# rev2.net
KiCad netlist of a schematic drawn in EAGLE
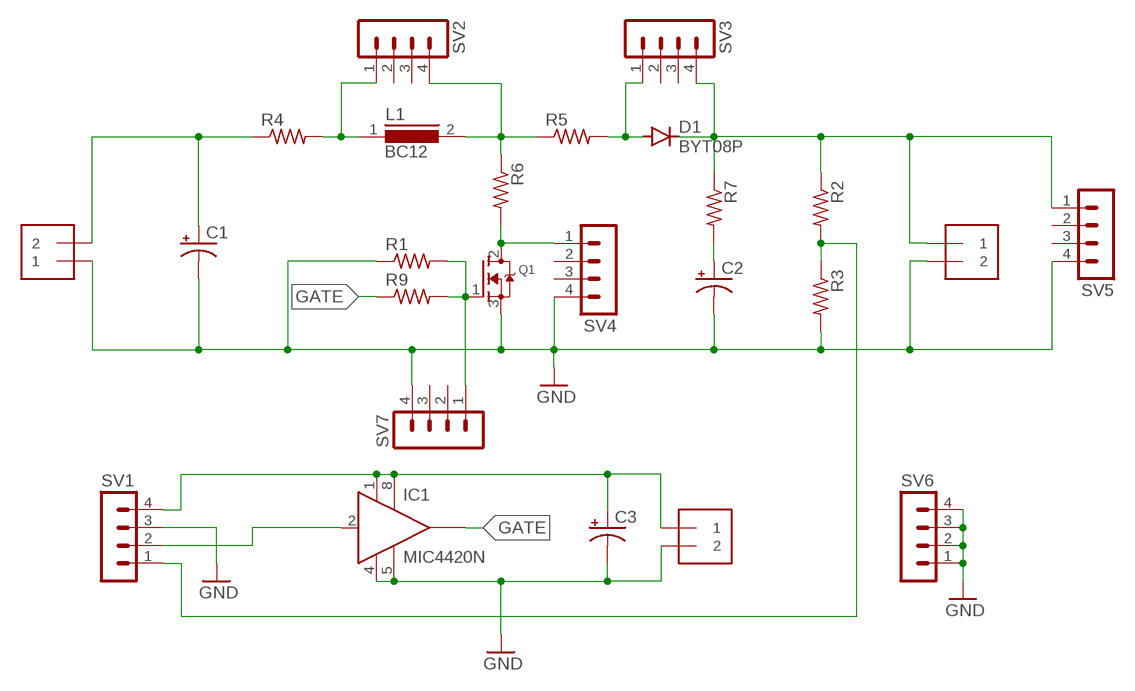
[diagram p0: schematic, sheet 1]

(export (version "E")
  (design (tool "Eeschema 10.0.6"))
  (components
    (comp (ref "C1")
      (value "CPOL-USE7.5-18")
      (footprint "eagle-import:E7,5-18")
      (libsource (lib "eagle-import") (part "CPOL-USE7.5-18"))
    )
    (comp (ref "C2")
      (value "CPOL-USE7.5-18")
      (footprint "eagle-import:E7,5-18")
      (libsource (lib "eagle-import") (part "CPOL-USE7.5-18"))
    )
    (comp (ref "C3")
      (value "CPOL-USE2.5-6")
      (footprint "eagle-import:E2,5-6")
      (libsource (lib "eagle-import") (part "CPOL-USE2.5-6"))
    )
    (comp (ref "D1")
      (value "BYT08P")
      (footprint "eagle-import:TO220ACS")
      (libsource (lib "eagle-import") (part "BYT08P"))
    )
    (comp (ref "IC1")
      (value "MIC4420N")
      (footprint "eagle-import:DIL08")
      (libsource (lib "eagle-import") (part "MIC4420N"))
    )
    (comp (ref "J1")
      (value "1X2-3.5MM")
      (footprint "eagle-import:1X2-3.5MM")
      (libsource (lib "eagle-import") (part "1X2-3.5MM"))
    )
    (comp (ref "J2")
      (value "1X2-3.5MM")
      (footprint "eagle-import:1X2-3.5MM")
      (libsource (lib "eagle-import") (part "1X2-3.5MM"))
    )
    (comp (ref "J3")
      (value "1X2-3.5MM")
      (footprint "eagle-import:1X2-3.5MM")
      (libsource (lib "eagle-import") (part "1X2-3.5MM"))
    )
    (comp (ref "L1")
      (value "BC12")
      (footprint "eagle-import:BC12")
      (libsource (lib "eagle-import") (part "BC12"))
    )
    (comp (ref "Q1")
      (value "MOSFET-NGDS_TO220V")
      (footprint "eagle-import:TO220V")
      (libsource (lib "eagle-import") (part "MOSFET-NGDS_TO220V"))
    )
    (comp (ref "R1")
      (value "R-US_0207/7")
      (footprint "eagle-import:0207_7")
      (libsource (lib "eagle-import") (part "R-US_0207/7"))
    )
    (comp (ref "R2")
      (value "R-US_0207/7")
      (footprint "eagle-import:0207_7")
      (libsource (lib "eagle-import") (part "R-US_0207/7"))
    )
    (comp (ref "R3")
      (value "R-US_0207/7")
      (footprint "eagle-import:0207_7")
      (libsource (lib "eagle-import") (part "R-US_0207/7"))
    )
    (comp (ref "R4")
      (value "R-US_0613/15")
      (footprint "eagle-import:P0613_15")
      (libsource (lib "eagle-import") (part "R-US_0613/15"))
    )
    (comp (ref "R5")
      (value "R-US_0613/15")
      (footprint "eagle-import:P0613_15")
      (libsource (lib "eagle-import") (part "R-US_0613/15"))
    )
    (comp (ref "R6")
      (value "R-US_0613/15")
      (footprint "eagle-import:P0613_15")
      (libsource (lib "eagle-import") (part "R-US_0613/15"))
    )
    (comp (ref "R7")
      (value "R-US_0613/15")
      (footprint "eagle-import:P0613_15")
      (libsource (lib "eagle-import") (part "R-US_0613/15"))
    )
    (comp (ref "R9")
      (value "R-US_0309/12")
      (footprint "eagle-import:0309_12")
      (libsource (lib "eagle-import") (part "R-US_0309/12"))
    )
    (comp (ref "SV1")
      (value "MA04-1")
      (footprint "eagle-import:MA04-1")
      (libsource (lib "eagle-import") (part "MA04-1"))
    )
    (comp (ref "SV2")
      (value "MA04-1")
      (footprint "eagle-import:MA04-1")
      (libsource (lib "eagle-import") (part "MA04-1"))
    )
    (comp (ref "SV3")
      (value "MA04-1")
      (footprint "eagle-import:MA04-1")
      (libsource (lib "eagle-import") (part "MA04-1"))
    )
    (comp (ref "SV4")
      (value "MA04-1")
      (footprint "eagle-import:MA04-1")
      (libsource (lib "eagle-import") (part "MA04-1"))
    )
    (comp (ref "SV5")
      (value "MA04-1")
      (footprint "eagle-import:MA04-1")
      (libsource (lib "eagle-import") (part "MA04-1"))
    )
    (comp (ref "SV6")
      (value "MA04-1")
      (footprint "eagle-import:MA04-1")
      (libsource (lib "eagle-import") (part "MA04-1"))
    )
    (comp (ref "SV7")
      (value "MA04-1")
      (footprint "eagle-import:MA04-1")
      (libsource (lib "eagle-import") (part "MA04-1"))
    )
  )
  (nets
    (net (code "1") (name "GATE") (class "Default")
      (node (ref "IC1") (pin "6") (pinfunction "OUT_6") (pintype "passive"))
      (node (ref "R9") (pin "1") (pinfunction "1_1") (pintype "passive"))
    )
    (net (code "2") (name "GND") (class "Default")
      (node (ref "C1") (pin "-") (pinfunction "-_-") (pintype "passive"))
      (node (ref "C2") (pin "-") (pinfunction "-_-") (pintype "passive"))
      (node (ref "C3") (pin "-") (pinfunction "-_-") (pintype "passive"))
      (node (ref "IC1") (pin "4") (pinfunction "GND_4") (pintype "power_in"))
      (node (ref "IC1") (pin "5") (pinfunction "GND1_5") (pintype "power_in"))
      (node (ref "J1") (pin "1") (pinfunction "1_1") (pintype "passive"))
      (node (ref "J2") (pin "2") (pinfunction "2_2") (pintype "passive"))
      (node (ref "J3") (pin "2") (pinfunction "2_2") (pintype "passive"))
      (node (ref "Q1") (pin "3") (pinfunction "S_3") (pintype "bidirectional"))
      (node (ref "R1") (pin "1") (pinfunction "1_1") (pintype "passive"))
      (node (ref "R3") (pin "2") (pinfunction "2_2") (pintype "passive"))
      (node (ref "SV1") (pin "3") (pinfunction "3_3") (pintype "passive"))
      (node (ref "SV4") (pin "4") (pinfunction "4_4") (pintype "passive"))
      (node (ref "SV5") (pin "4") (pinfunction "4_4") (pintype "passive"))
      (node (ref "SV6") (pin "1") (pinfunction "1_1") (pintype "passive"))
      (node (ref "SV6") (pin "2") (pinfunction "2_2") (pintype "passive"))
      (node (ref "SV6") (pin "3") (pinfunction "3_3") (pintype "passive"))
      (node (ref "SV6") (pin "4") (pinfunction "4_4") (pintype "passive"))
      (node (ref "SV7") (pin "4") (pinfunction "4_4") (pintype "passive"))
    )
    (net (code "3") (name "Net-(C1-Pad+)") (class "Default")
      (node (ref "C1") (pin "+") (pinfunction "+_+") (pintype "passive"))
      (node (ref "J1") (pin "2") (pinfunction "2_2") (pintype "passive"))
      (node (ref "R4") (pin "1") (pinfunction "1_1") (pintype "passive"))
    )
    (net (code "4") (name "Net-(C2-Pad+)") (class "Default")
      (node (ref "C2") (pin "+") (pinfunction "+_+") (pintype "passive"))
      (node (ref "R7") (pin "2") (pinfunction "2_2") (pintype "passive"))
    )
    (net (code "5") (name "Net-(D1-PadA)") (class "Default")
      (node (ref "D1") (pin "A") (pinfunction "A_A") (pintype "passive"))
      (node (ref "R5") (pin "2") (pinfunction "2_2") (pintype "passive"))
      (node (ref "SV3") (pin "1") (pinfunction "1_1") (pintype "passive"))
    )
    (net (code "6") (name "Net-(D1-PadC)") (class "Default")
      (node (ref "D1") (pin "C") (pinfunction "C_C") (pintype "passive"))
      (node (ref "J2") (pin "1") (pinfunction "1_1") (pintype "passive"))
      (node (ref "R2") (pin "1") (pinfunction "1_1") (pintype "passive"))
      (node (ref "R7") (pin "1") (pinfunction "1_1") (pintype "passive"))
      (node (ref "SV3") (pin "4") (pinfunction "4_4") (pintype "passive"))
      (node (ref "SV5") (pin "1") (pinfunction "1_1") (pintype "passive"))
    )
    (net (code "7") (name "Net-(IC1-IN)") (class "Default")
      (node (ref "IC1") (pin "2") (pinfunction "IN_2") (pintype "input"))
      (node (ref "SV1") (pin "2") (pinfunction "2_2") (pintype "passive"))
    )
    (net (code "8") (name "Net-(IC1-VS)") (class "Default")
      (node (ref "C3") (pin "+") (pinfunction "+_+") (pintype "passive"))
      (node (ref "IC1") (pin "1") (pinfunction "VS_1") (pintype "power_in"))
      (node (ref "IC1") (pin "8") (pinfunction "VS1_8") (pintype "power_in"))
      (node (ref "J3") (pin "1") (pinfunction "1_1") (pintype "passive"))
      (node (ref "SV1") (pin "4") (pinfunction "4_4") (pintype "passive"))
    )
    (net (code "9") (name "Net-(L1-Pad1)") (class "Default")
      (node (ref "L1") (pin "1") (pinfunction "1_1") (pintype "passive"))
      (node (ref "R4") (pin "2") (pinfunction "2_2") (pintype "passive"))
      (node (ref "SV2") (pin "1") (pinfunction "1_1") (pintype "passive"))
    )
    (net (code "10") (name "Net-(L1-Pad2)") (class "Default")
      (node (ref "L1") (pin "2") (pinfunction "2_2") (pintype "passive"))
      (node (ref "R5") (pin "1") (pinfunction "1_1") (pintype "passive"))
      (node (ref "R6") (pin "1") (pinfunction "1_1") (pintype "passive"))
      (node (ref "SV2") (pin "4") (pinfunction "4_4") (pintype "passive"))
    )
    (net (code "11") (name "Net-(Q1-D)") (class "Default")
      (node (ref "Q1") (pin "2") (pinfunction "D_2") (pintype "bidirectional"))
      (node (ref "R6") (pin "2") (pinfunction "2_2") (pintype "passive"))
      (node (ref "SV4") (pin "1") (pinfunction "1_1") (pintype "passive"))
    )
    (net (code "12") (name "Net-(Q1-G)") (class "Default")
      (node (ref "Q1") (pin "1") (pinfunction "G_1") (pintype "bidirectional"))
      (node (ref "R1") (pin "2") (pinfunction "2_2") (pintype "passive"))
      (node (ref "R9") (pin "2") (pinfunction "2_2") (pintype "passive"))
      (node (ref "SV7") (pin "1") (pinfunction "1_1") (pintype "passive"))
    )
    (net (code "13") (name "Net-(R2-Pad2)") (class "Default")
      (node (ref "R2") (pin "2") (pinfunction "2_2") (pintype "passive"))
      (node (ref "R3") (pin "1") (pinfunction "1_1") (pintype "passive"))
      (node (ref "SV1") (pin "1") (pinfunction "1_1") (pintype "passive"))
    )
    (net (code "14") (name "unconnected-(IC1-OUT-Pad7)") (class "Default")
      (node (ref "IC1") (pin "7") (pinfunction "OUT_7") (pintype "passive"))
    )
    (net (code "15") (name "unconnected-(SV2-Pad2)") (class "Default")
      (node (ref "SV2") (pin "2") (pinfunction "2_2") (pintype "passive"))
    )
    (net (code "16") (name "unconnected-(SV2-Pad3)") (class "Default")
      (node (ref "SV2") (pin "3") (pinfunction "3_3") (pintype "passive"))
    )
    (net (code "17") (name "unconnected-(SV3-Pad2)") (class "Default")
      (node (ref "SV3") (pin "2") (pinfunction "2_2") (pintype "passive"))
    )
    (net (code "18") (name "unconnected-(SV3-Pad3)") (class "Default")
      (node (ref "SV3") (pin "3") (pinfunction "3_3") (pintype "passive"))
    )
    (net (code "19") (name "unconnected-(SV4-Pad2)") (class "Default")
      (node (ref "SV4") (pin "2") (pinfunction "2_2") (pintype "passive"))
    )
    (net (code "20") (name "unconnected-(SV4-Pad3)") (class "Default")
      (node (ref "SV4") (pin "3") (pinfunction "3_3") (pintype "passive"))
    )
    (net (code "21") (name "unconnected-(SV5-Pad2)") (class "Default")
      (node (ref "SV5") (pin "2") (pinfunction "2_2") (pintype "passive"))
    )
    (net (code "22") (name "unconnected-(SV5-Pad3)") (class "Default")
      (node (ref "SV5") (pin "3") (pinfunction "3_3") (pintype "passive"))
    )
    (net (code "23") (name "unconnected-(SV7-Pad2)") (class "Default")
      (node (ref "SV7") (pin "2") (pinfunction "2_2") (pintype "passive"))
    )
    (net (code "24") (name "unconnected-(SV7-Pad3)") (class "Default")
      (node (ref "SV7") (pin "3") (pinfunction "3_3") (pintype "passive"))
    )
  )
)
